# LSM6DSRXTR.net
KiCad netlist of a schematic drawn in Altium Designer
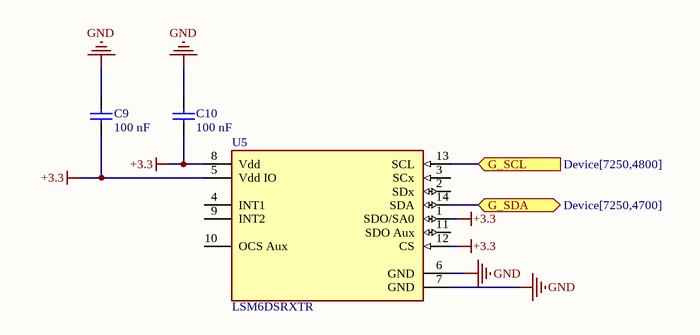
[diagram p0: LSM6DSRXTR.SchDoc]

(export (version "E")
  (design (tool "Eeschema 10.0.6"))
  (components
    (comp (ref "C9")
      (value "100 nF")
      (footprint "CAPC1005X55X25NL05T10")
      (fields (field (name "MANUFACTURER") "Murata") (field (name "PART NUMBER") "GRM155F50J684ZE01D"))
      (libsource (lib "Altium Content Vault") (part "CAP"))
    )
    (comp (ref "C10")
      (value "100 nF")
      (footprint "CAPC1005X55X25NL05T10")
      (fields (field (name "MANUFACTURER") "Murata") (field (name "PART NUMBER") "GRM155F50J684ZE01D"))
      (libsource (lib "Altium Content Vault") (part "CAP"))
    )
    (comp (ref "U5")
      (value "LSM6DSRXTR")
      (footprint "FP-LGA-14L-DM00249496-MFG")
      (description "CONSUMER MEMS")
      (libsource (lib "Altium Content Vault") (part "541766176f9193a0aeca2d3d8f6bee9"))
    )
  )
  (nets
    (net (code "1") (name "+3.3") (class "Default")
      (node (ref "C10") (pin "2") (pinfunction "2_2") (pintype "passive"))
      (node (ref "C9") (pin "2") (pinfunction "2_2") (pintype "passive"))
      (node (ref "U5") (pin "1") (pinfunction "SDO/SA0_1") (pintype "bidirectional"))
      (node (ref "U5") (pin "12") (pinfunction "CS_12") (pintype "input"))
      (node (ref "U5") (pin "5") (pinfunction "Vdd_IO_5") (pintype "power_in"))
      (node (ref "U5") (pin "8") (pinfunction "Vdd_8") (pintype "power_in"))
    )
    (net (code "2") (name "/G_SCL") (class "Default")
      (node (ref "U5") (pin "13") (pinfunction "SCL_13") (pintype "input"))
    )
    (net (code "3") (name "/G_SDA") (class "Default")
      (node (ref "U5") (pin "14") (pinfunction "SDA_14") (pintype "bidirectional"))
    )
    (net (code "4") (name "GND") (class "Default")
      (node (ref "C10") (pin "1") (pinfunction "1_1") (pintype "passive"))
      (node (ref "C9") (pin "1") (pinfunction "1_1") (pintype "passive"))
      (node (ref "U5") (pin "6") (pinfunction "GND_6") (pintype "power_in"))
      (node (ref "U5") (pin "7") (pinfunction "GND_7") (pintype "power_in"))
    )
    (net (code "5") (name "unconnected-(U5-INT1-Pad4)") (class "Default")
      (node (ref "U5") (pin "4") (pinfunction "INT1_4") (pintype "passive"))
    )
    (net (code "6") (name "unconnected-(U5-INT2-Pad9)") (class "Default")
      (node (ref "U5") (pin "9") (pinfunction "INT2_9") (pintype "passive"))
    )
    (net (code "7") (name "unconnected-(U5-OCS_Aux-Pad10)") (class "Default")
      (node (ref "U5") (pin "10") (pinfunction "OCS_Aux_10") (pintype "passive"))
    )
    (net (code "8") (name "unconnected-(U5-SCx-Pad3)") (class "Default")
      (node (ref "U5") (pin "3") (pinfunction "SCx_3") (pintype "input"))
    )
    (net (code "9") (name "unconnected-(U5-SDO_Aux-Pad11)") (class "Default")
      (node (ref "U5") (pin "11") (pinfunction "SDO_Aux_11") (pintype "bidirectional"))
    )
    (net (code "10") (name "unconnected-(U5-SDx-Pad2)") (class "Default")
      (node (ref "U5") (pin "2") (pinfunction "SDx_2") (pintype "bidirectional"))
    )
  )
)
